# relay.net
KiCad netlist of a schematic drawn in Altium Designer
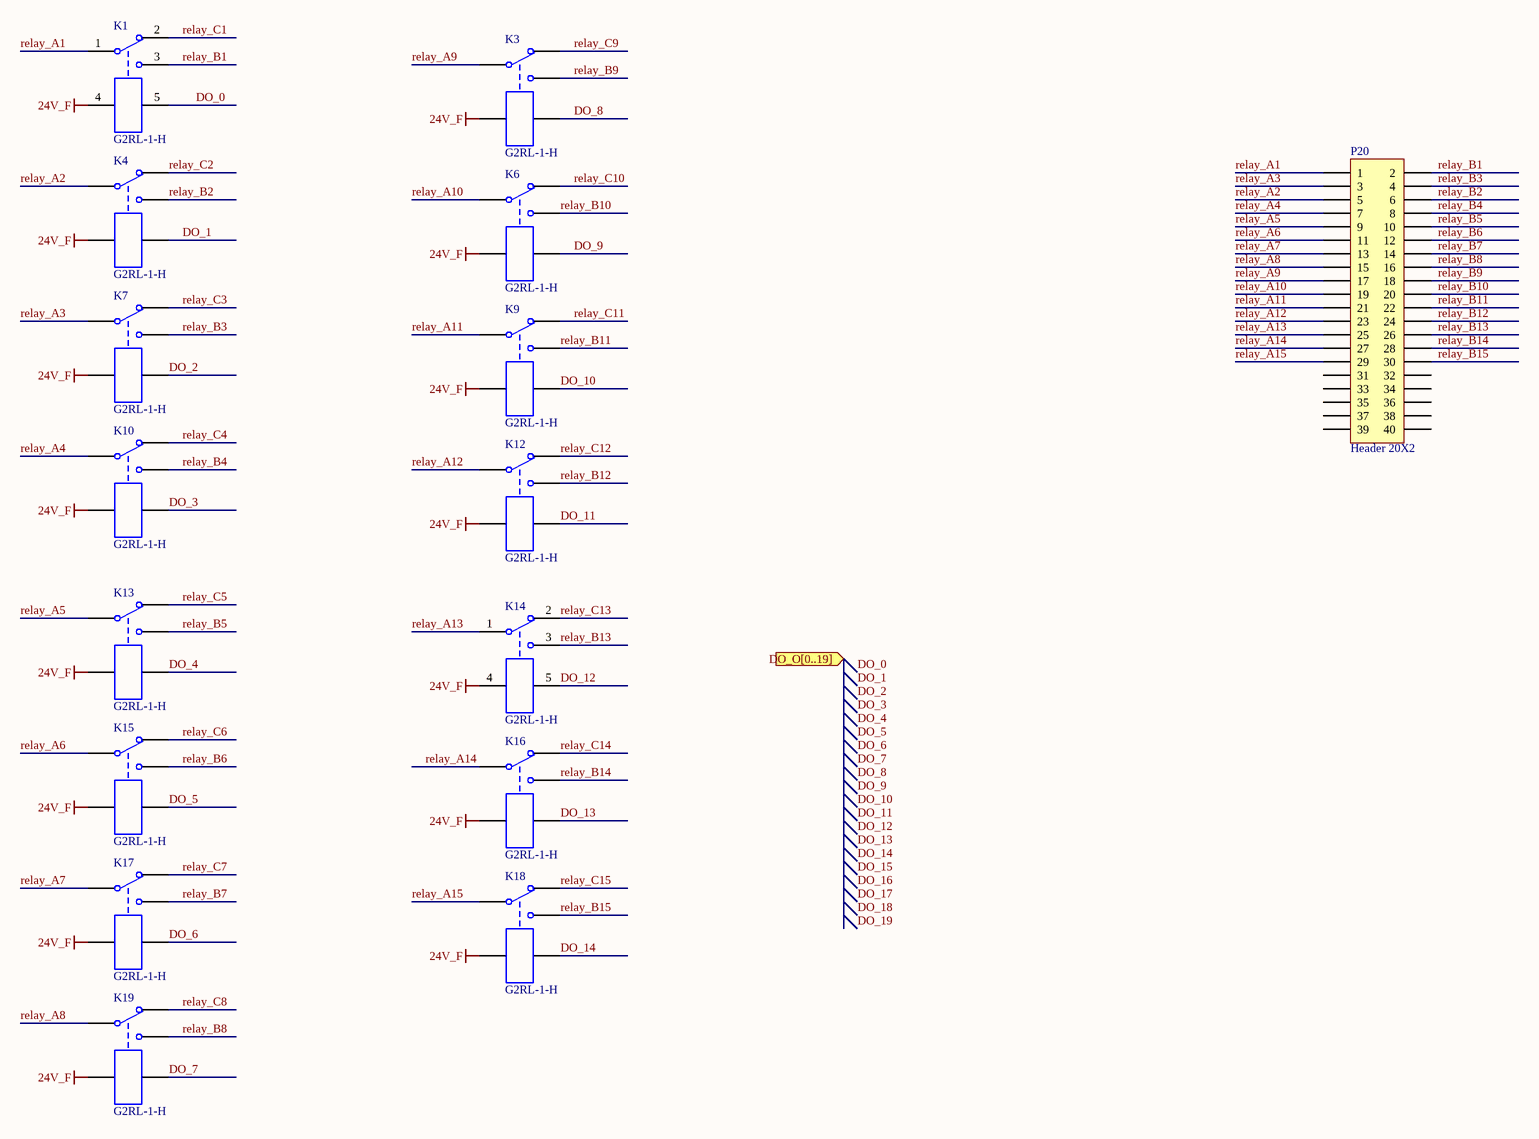
[diagram p0: relay.SchDoc]

(export (version "E")
  (design (tool "Eeschema 10.0.6"))
  (components
    (comp (ref "K1")
      (value "G2RL-1-H")
      (footprint "G2RL-1-H")
      (description "Single-Pole Dual-Throw Relay")
      (fields (field (name "PUBLISHER") "Altium Limited"))
      (libsource (lib "") (part "Relay-SPDT_1"))
    )
    (comp (ref "K3")
      (value "G2RL-1-H")
      (footprint "G2RL-1-H")
      (description "Single-Pole Dual-Throw Relay")
      (fields (field (name "PUBLISHER") "Altium Limited"))
      (libsource (lib "Miscellaneous Devices") (part "Relay-SPDT"))
    )
    (comp (ref "K4")
      (value "G2RL-1-H")
      (footprint "G2RL-1-H")
      (description "Single-Pole Dual-Throw Relay")
      (fields (field (name "PUBLISHER") "Altium Limited"))
      (libsource (lib "Miscellaneous Devices") (part "Relay-SPDT"))
    )
    (comp (ref "K6")
      (value "G2RL-1-H")
      (footprint "G2RL-1-H")
      (description "Single-Pole Dual-Throw Relay")
      (fields (field (name "PUBLISHER") "Altium Limited"))
      (libsource (lib "Miscellaneous Devices") (part "Relay-SPDT"))
    )
    (comp (ref "K7")
      (value "G2RL-1-H")
      (footprint "G2RL-1-H")
      (description "Single-Pole Dual-Throw Relay")
      (fields (field (name "PUBLISHER") "Altium Limited"))
      (libsource (lib "Miscellaneous Devices") (part "Relay-SPDT"))
    )
    (comp (ref "K9")
      (value "G2RL-1-H")
      (footprint "G2RL-1-H")
      (description "Single-Pole Dual-Throw Relay")
      (fields (field (name "PUBLISHER") "Altium Limited"))
      (libsource (lib "Miscellaneous Devices") (part "Relay-SPDT"))
    )
    (comp (ref "K10")
      (value "G2RL-1-H")
      (footprint "G2RL-1-H")
      (description "Single-Pole Dual-Throw Relay")
      (fields (field (name "PUBLISHER") "Altium Limited"))
      (libsource (lib "Miscellaneous Devices") (part "Relay-SPDT"))
    )
    (comp (ref "K12")
      (value "G2RL-1-H")
      (footprint "G2RL-1-H")
      (description "Single-Pole Dual-Throw Relay")
      (fields (field (name "PUBLISHER") "Altium Limited"))
      (libsource (lib "Miscellaneous Devices") (part "Relay-SPDT"))
    )
    (comp (ref "K13")
      (value "G2RL-1-H")
      (footprint "G2RL-1-H")
      (description "Single-Pole Dual-Throw Relay")
      (fields (field (name "PUBLISHER") "Altium Limited"))
      (libsource (lib "Miscellaneous Devices") (part "Relay-SPDT"))
    )
    (comp (ref "K14")
      (value "G2RL-1-H")
      (footprint "G2RL-1-H")
      (description "Single-Pole Dual-Throw Relay")
      (fields (field (name "PUBLISHER") "Altium Limited"))
      (libsource (lib "") (part "Relay-SPDT_1"))
    )
    (comp (ref "K15")
      (value "G2RL-1-H")
      (footprint "G2RL-1-H")
      (description "Single-Pole Dual-Throw Relay")
      (fields (field (name "PUBLISHER") "Altium Limited"))
      (libsource (lib "Miscellaneous Devices") (part "Relay-SPDT"))
    )
    (comp (ref "K16")
      (value "G2RL-1-H")
      (footprint "G2RL-1-H")
      (description "Single-Pole Dual-Throw Relay")
      (fields (field (name "PUBLISHER") "Altium Limited"))
      (libsource (lib "Miscellaneous Devices") (part "Relay-SPDT"))
    )
    (comp (ref "K17")
      (value "G2RL-1-H")
      (footprint "G2RL-1-H")
      (description "Single-Pole Dual-Throw Relay")
      (fields (field (name "PUBLISHER") "Altium Limited"))
      (libsource (lib "Miscellaneous Devices") (part "Relay-SPDT"))
    )
    (comp (ref "K18")
      (value "G2RL-1-H")
      (footprint "G2RL-1-H")
      (description "Single-Pole Dual-Throw Relay")
      (fields (field (name "PUBLISHER") "Altium Limited"))
      (libsource (lib "Miscellaneous Devices") (part "Relay-SPDT"))
    )
    (comp (ref "K19")
      (value "G2RL-1-H")
      (footprint "G2RL-1-H")
      (description "Single-Pole Dual-Throw Relay")
      (fields (field (name "PUBLISHER") "Altium Limited"))
      (libsource (lib "Miscellaneous Devices") (part "Relay-SPDT"))
    )
    (comp (ref "P20")
      (value "Header 20X2")
      (footprint "XH2.54_2x20")
      (description "Header, 20-Pin, Dual row")
      (fields (field (name "PUBLISHER") "Altium Limited"))
      (libsource (lib "Miscellaneous Connectors") (part "Header 20X2"))
    )
  )
  (nets
    (net (code "21") (name "/DO_0") (class "Default")
      (node (ref "K1") (pin "5") (pinfunction "5_5") (pintype "passive"))
    )
    (net (code "22") (name "/DO_1") (class "Default")
      (node (ref "K4") (pin "5") (pinfunction "5_5") (pintype "passive"))
    )
    (net (code "23") (name "/DO_2") (class "Default")
      (node (ref "K7") (pin "5") (pinfunction "5_5") (pintype "passive"))
    )
    (net (code "24") (name "/DO_3") (class "Default")
      (node (ref "K10") (pin "5") (pinfunction "5_5") (pintype "passive"))
    )
    (net (code "25") (name "/DO_4") (class "Default")
      (node (ref "K13") (pin "5") (pinfunction "5_5") (pintype "passive"))
    )
    (net (code "26") (name "/DO_5") (class "Default")
      (node (ref "K15") (pin "5") (pinfunction "5_5") (pintype "passive"))
    )
    (net (code "27") (name "/DO_6") (class "Default")
      (node (ref "K17") (pin "5") (pinfunction "5_5") (pintype "passive"))
    )
    (net (code "28") (name "/DO_7") (class "Default")
      (node (ref "K19") (pin "5") (pinfunction "5_5") (pintype "passive"))
    )
    (net (code "29") (name "/DO_8") (class "Default")
      (node (ref "K3") (pin "5") (pinfunction "5_5") (pintype "passive"))
    )
    (net (code "30") (name "/DO_9") (class "Default")
      (node (ref "K6") (pin "5") (pinfunction "5_5") (pintype "passive"))
    )
    (net (code "31") (name "/DO_10") (class "Default")
      (node (ref "K9") (pin "5") (pinfunction "5_5") (pintype "passive"))
    )
    (net (code "32") (name "/DO_11") (class "Default")
      (node (ref "K12") (pin "5") (pinfunction "5_5") (pintype "passive"))
    )
    (net (code "33") (name "/DO_12") (class "Default")
      (node (ref "K14") (pin "5") (pinfunction "5_5") (pintype "passive"))
    )
    (net (code "34") (name "/DO_13") (class "Default")
      (node (ref "K16") (pin "5") (pinfunction "5_5") (pintype "passive"))
    )
    (net (code "35") (name "/DO_14") (class "Default")
      (node (ref "K18") (pin "5") (pinfunction "5_5") (pintype "passive"))
    )
    (net (code "42") (name "/relay_A1") (class "Default")
      (node (ref "K1") (pin "1") (pinfunction "1_1") (pintype "passive"))
      (node (ref "P20") (pin "1") (pinfunction "1_1") (pintype "passive"))
    )
    (net (code "43") (name "/relay_A2") (class "Default")
      (node (ref "K4") (pin "1") (pinfunction "1_1") (pintype "passive"))
      (node (ref "P20") (pin "5") (pinfunction "5_5") (pintype "passive"))
    )
    (net (code "44") (name "/relay_A3") (class "Default")
      (node (ref "K7") (pin "1") (pinfunction "1_1") (pintype "passive"))
      (node (ref "P20") (pin "3") (pinfunction "3_3") (pintype "passive"))
    )
    (net (code "45") (name "/relay_A4") (class "Default")
      (node (ref "K10") (pin "1") (pinfunction "1_1") (pintype "passive"))
      (node (ref "P20") (pin "7") (pinfunction "7_7") (pintype "passive"))
    )
    (net (code "46") (name "/relay_A5") (class "Default")
      (node (ref "K13") (pin "1") (pinfunction "1_1") (pintype "passive"))
      (node (ref "P20") (pin "9") (pinfunction "9_9") (pintype "passive"))
    )
    (net (code "47") (name "/relay_A6") (class "Default")
      (node (ref "K15") (pin "1") (pinfunction "1_1") (pintype "passive"))
      (node (ref "P20") (pin "11") (pinfunction "11_11") (pintype "passive"))
    )
    (net (code "48") (name "/relay_A7") (class "Default")
      (node (ref "K17") (pin "1") (pinfunction "1_1") (pintype "passive"))
      (node (ref "P20") (pin "13") (pinfunction "13_13") (pintype "passive"))
    )
    (net (code "49") (name "/relay_A8") (class "Default")
      (node (ref "K19") (pin "1") (pinfunction "1_1") (pintype "passive"))
      (node (ref "P20") (pin "15") (pinfunction "15_15") (pintype "passive"))
    )
    (net (code "50") (name "/relay_A9") (class "Default")
      (node (ref "K3") (pin "1") (pinfunction "1_1") (pintype "passive"))
      (node (ref "P20") (pin "17") (pinfunction "17_17") (pintype "passive"))
    )
    (net (code "51") (name "/relay_A10") (class "Default")
      (node (ref "K6") (pin "1") (pinfunction "1_1") (pintype "passive"))
      (node (ref "P20") (pin "19") (pinfunction "19_19") (pintype "passive"))
    )
    (net (code "52") (name "/relay_A11") (class "Default")
      (node (ref "K9") (pin "1") (pinfunction "1_1") (pintype "passive"))
      (node (ref "P20") (pin "21") (pinfunction "21_21") (pintype "passive"))
    )
    (net (code "53") (name "/relay_A12") (class "Default")
      (node (ref "K12") (pin "1") (pinfunction "1_1") (pintype "passive"))
      (node (ref "P20") (pin "23") (pinfunction "23_23") (pintype "passive"))
    )
    (net (code "54") (name "/relay_A13") (class "Default")
      (node (ref "K14") (pin "1") (pinfunction "1_1") (pintype "passive"))
      (node (ref "P20") (pin "25") (pinfunction "25_25") (pintype "passive"))
    )
    (net (code "55") (name "/relay_A14") (class "Default")
      (node (ref "K16") (pin "1") (pinfunction "1_1") (pintype "passive"))
      (node (ref "P20") (pin "27") (pinfunction "27_27") (pintype "passive"))
    )
    (net (code "56") (name "/relay_A15") (class "Default")
      (node (ref "K18") (pin "1") (pinfunction "1_1") (pintype "passive"))
      (node (ref "P20") (pin "29") (pinfunction "29_29") (pintype "passive"))
    )
    (net (code "57") (name "/relay_B1") (class "Default")
      (node (ref "K1") (pin "3") (pinfunction "3_3") (pintype "passive"))
      (node (ref "P20") (pin "2") (pinfunction "2_2") (pintype "passive"))
    )
    (net (code "58") (name "/relay_B2") (class "Default")
      (node (ref "K4") (pin "3") (pinfunction "3_3") (pintype "passive"))
      (node (ref "P20") (pin "6") (pinfunction "6_6") (pintype "passive"))
    )
    (net (code "59") (name "/relay_B3") (class "Default")
      (node (ref "K7") (pin "3") (pinfunction "3_3") (pintype "passive"))
      (node (ref "P20") (pin "4") (pinfunction "4_4") (pintype "passive"))
    )
    (net (code "60") (name "/relay_B4") (class "Default")
      (node (ref "K10") (pin "3") (pinfunction "3_3") (pintype "passive"))
      (node (ref "P20") (pin "8") (pinfunction "8_8") (pintype "passive"))
    )
    (net (code "61") (name "/relay_B5") (class "Default")
      (node (ref "K13") (pin "3") (pinfunction "3_3") (pintype "passive"))
      (node (ref "P20") (pin "10") (pinfunction "10_10") (pintype "passive"))
    )
    (net (code "62") (name "/relay_B6") (class "Default")
      (node (ref "K15") (pin "3") (pinfunction "3_3") (pintype "passive"))
      (node (ref "P20") (pin "12") (pinfunction "12_12") (pintype "passive"))
    )
    (net (code "63") (name "/relay_B7") (class "Default")
      (node (ref "K17") (pin "3") (pinfunction "3_3") (pintype "passive"))
      (node (ref "P20") (pin "14") (pinfunction "14_14") (pintype "passive"))
    )
    (net (code "64") (name "/relay_B8") (class "Default")
      (node (ref "K19") (pin "3") (pinfunction "3_3") (pintype "passive"))
      (node (ref "P20") (pin "16") (pinfunction "16_16") (pintype "passive"))
    )
    (net (code "65") (name "/relay_B9") (class "Default")
      (node (ref "K3") (pin "3") (pinfunction "3_3") (pintype "passive"))
      (node (ref "P20") (pin "18") (pinfunction "18_18") (pintype "passive"))
    )
    (net (code "66") (name "/relay_B10") (class "Default")
      (node (ref "K6") (pin "3") (pinfunction "3_3") (pintype "passive"))
      (node (ref "P20") (pin "20") (pinfunction "20_20") (pintype "passive"))
    )
    (net (code "67") (name "/relay_B11") (class "Default")
      (node (ref "K9") (pin "3") (pinfunction "3_3") (pintype "passive"))
      (node (ref "P20") (pin "22") (pinfunction "22_22") (pintype "passive"))
    )
    (net (code "68") (name "/relay_B12") (class "Default")
      (node (ref "K12") (pin "3") (pinfunction "3_3") (pintype "passive"))
      (node (ref "P20") (pin "24") (pinfunction "24_24") (pintype "passive"))
    )
    (net (code "69") (name "/relay_B13") (class "Default")
      (node (ref "K14") (pin "3") (pinfunction "3_3") (pintype "passive"))
      (node (ref "P20") (pin "26") (pinfunction "26_26") (pintype "passive"))
    )
    (net (code "70") (name "/relay_B14") (class "Default")
      (node (ref "K16") (pin "3") (pinfunction "3_3") (pintype "passive"))
      (node (ref "P20") (pin "28") (pinfunction "28_28") (pintype "passive"))
    )
    (net (code "71") (name "/relay_B15") (class "Default")
      (node (ref "K18") (pin "3") (pinfunction "3_3") (pintype "passive"))
      (node (ref "P20") (pin "30") (pinfunction "30_30") (pintype "passive"))
    )
    (net (code "72") (name "/relay_C1") (class "Default")
      (node (ref "K1") (pin "2") (pinfunction "2_2") (pintype "passive"))
    )
    (net (code "73") (name "/relay_C2") (class "Default")
      (node (ref "K4") (pin "2") (pinfunction "2_2") (pintype "passive"))
    )
    (net (code "74") (name "/relay_C3") (class "Default")
      (node (ref "K7") (pin "2") (pinfunction "2_2") (pintype "passive"))
    )
    (net (code "75") (name "/relay_C4") (class "Default")
      (node (ref "K10") (pin "2") (pinfunction "2_2") (pintype "passive"))
    )
    (net (code "76") (name "/relay_C5") (class "Default")
      (node (ref "K13") (pin "2") (pinfunction "2_2") (pintype "passive"))
    )
    (net (code "77") (name "/relay_C6") (class "Default")
      (node (ref "K15") (pin "2") (pinfunction "2_2") (pintype "passive"))
    )
    (net (code "78") (name "/relay_C7") (class "Default")
      (node (ref "K17") (pin "2") (pinfunction "2_2") (pintype "passive"))
    )
    (net (code "79") (name "/relay_C8") (class "Default")
      (node (ref "K19") (pin "2") (pinfunction "2_2") (pintype "passive"))
    )
    (net (code "80") (name "/relay_C9") (class "Default")
      (node (ref "K3") (pin "2") (pinfunction "2_2") (pintype "passive"))
    )
    (net (code "81") (name "/relay_C10") (class "Default")
      (node (ref "K6") (pin "2") (pinfunction "2_2") (pintype "passive"))
    )
    (net (code "82") (name "/relay_C11") (class "Default")
      (node (ref "K9") (pin "2") (pinfunction "2_2") (pintype "passive"))
    )
    (net (code "83") (name "/relay_C12") (class "Default")
      (node (ref "K12") (pin "2") (pinfunction "2_2") (pintype "passive"))
    )
    (net (code "84") (name "/relay_C13") (class "Default")
      (node (ref "K14") (pin "2") (pinfunction "2_2") (pintype "passive"))
    )
    (net (code "85") (name "/relay_C14") (class "Default")
      (node (ref "K16") (pin "2") (pinfunction "2_2") (pintype "passive"))
    )
    (net (code "86") (name "/relay_C15") (class "Default")
      (node (ref "K18") (pin "2") (pinfunction "2_2") (pintype "passive"))
    )
    (net (code "87") (name "24V_F") (class "Default")
      (node (ref "K1") (pin "4") (pinfunction "4_4") (pintype "passive"))
      (node (ref "K10") (pin "4") (pinfunction "4_4") (pintype "passive"))
      (node (ref "K12") (pin "4") (pinfunction "4_4") (pintype "passive"))
      (node (ref "K13") (pin "4") (pinfunction "4_4") (pintype "passive"))
      (node (ref "K14") (pin "4") (pinfunction "4_4") (pintype "passive"))
      (node (ref "K15") (pin "4") (pinfunction "4_4") (pintype "passive"))
      (node (ref "K16") (pin "4") (pinfunction "4_4") (pintype "passive"))
      (node (ref "K17") (pin "4") (pinfunction "4_4") (pintype "passive"))
      (node (ref "K18") (pin "4") (pinfunction "4_4") (pintype "passive"))
      (node (ref "K19") (pin "4") (pinfunction "4_4") (pintype "passive"))
      (node (ref "K3") (pin "4") (pinfunction "4_4") (pintype "passive"))
      (node (ref "K4") (pin "4") (pinfunction "4_4") (pintype "passive"))
      (node (ref "K6") (pin "4") (pinfunction "4_4") (pintype "passive"))
      (node (ref "K7") (pin "4") (pinfunction "4_4") (pintype "passive"))
      (node (ref "K9") (pin "4") (pinfunction "4_4") (pintype "passive"))
    )
    (net (code "88") (name "unconnected-(P20-Pad31)") (class "Default")
      (node (ref "P20") (pin "31") (pinfunction "31_31") (pintype "passive"))
    )
    (net (code "89") (name "unconnected-(P20-Pad32)") (class "Default")
      (node (ref "P20") (pin "32") (pinfunction "32_32") (pintype "passive"))
    )
    (net (code "90") (name "unconnected-(P20-Pad33)") (class "Default")
      (node (ref "P20") (pin "33") (pinfunction "33_33") (pintype "passive"))
    )
    (net (code "91") (name "unconnected-(P20-Pad34)") (class "Default")
      (node (ref "P20") (pin "34") (pinfunction "34_34") (pintype "passive"))
    )
    (net (code "92") (name "unconnected-(P20-Pad35)") (class "Default")
      (node (ref "P20") (pin "35") (pinfunction "35_35") (pintype "passive"))
    )
    (net (code "93") (name "unconnected-(P20-Pad36)") (class "Default")
      (node (ref "P20") (pin "36") (pinfunction "36_36") (pintype "passive"))
    )
    (net (code "94") (name "unconnected-(P20-Pad37)") (class "Default")
      (node (ref "P20") (pin "37") (pinfunction "37_37") (pintype "passive"))
    )
    (net (code "95") (name "unconnected-(P20-Pad38)") (class "Default")
      (node (ref "P20") (pin "38") (pinfunction "38_38") (pintype "passive"))
    )
    (net (code "96") (name "unconnected-(P20-Pad39)") (class "Default")
      (node (ref "P20") (pin "39") (pinfunction "39_39") (pintype "passive"))
    )
    (net (code "97") (name "unconnected-(P20-Pad40)") (class "Default")
      (node (ref "P20") (pin "40") (pinfunction "40_40") (pintype "passive"))
    )
  )
)
